# Hoff.net
KiCad netlist of a schematic drawn in EAGLE
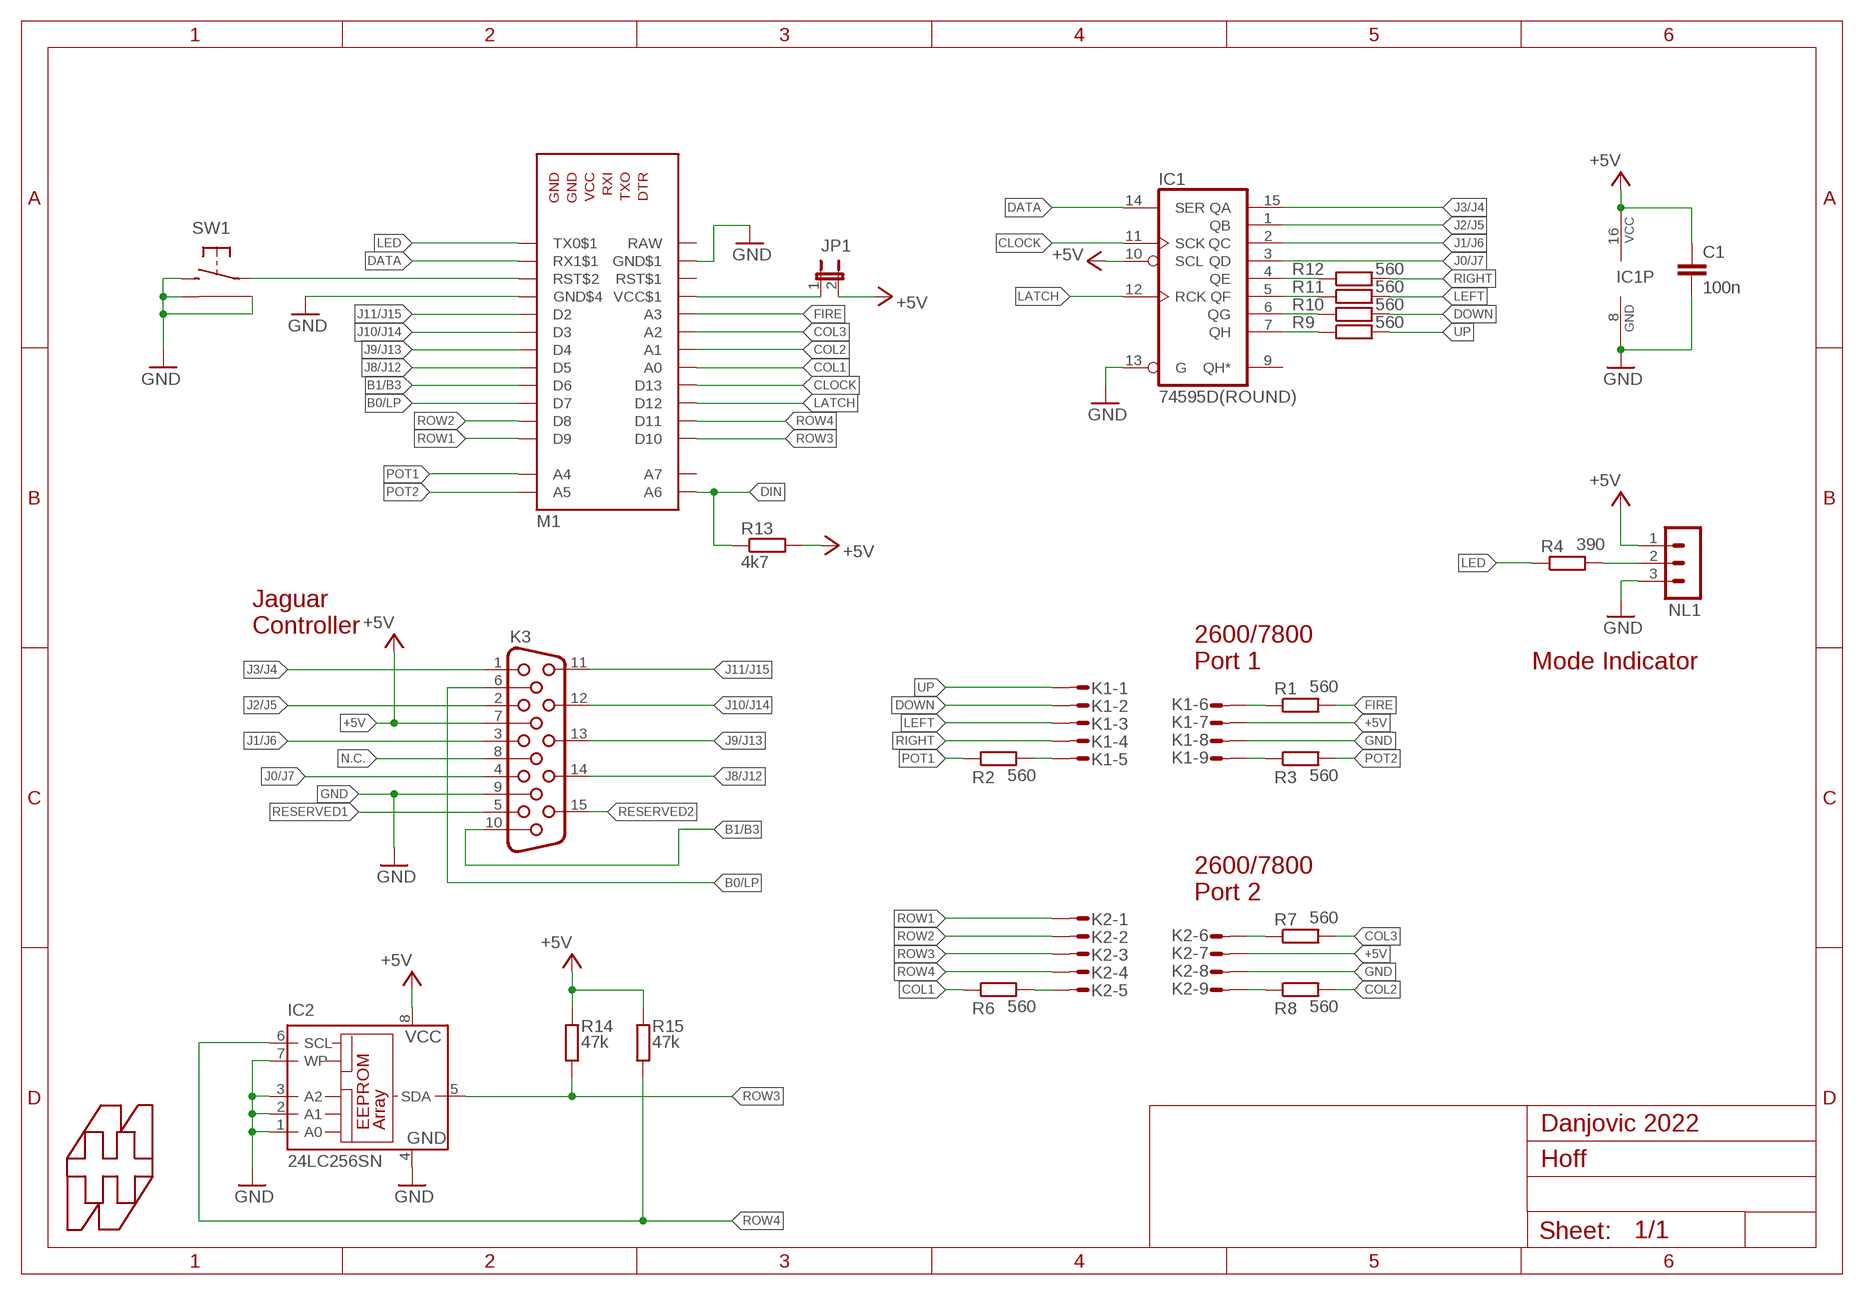
[diagram p0: schematic, sheet 1]

(export (version "E")
  (design (tool "Eeschema 10.0.6"))
  (components
    (comp (ref "C1")
      (value "100n")
      (footprint "eagle-import:C050-024X044")
      (libsource (lib "eagle-import") (part "C-EU050-024X044"))
    )
    (comp (ref "IC1")
      (value "74595D(ROUND)")
      (footprint "eagle-import:DIL16-ROUND")
      (libsource (lib "eagle-import") (part "74595D(ROUND)"))
    )
    (comp (ref "IC2")
      (value "24LC256SN")
      (footprint "eagle-import:SO-08")
      (fields (field (name "MF") "MICROCHIP") (field (name "MPN") "24LC256-I/SN"))
      (libsource (lib "eagle-import") (part "24SNLC256"))
    )
    (comp (ref "JP1")
      (value "JP1E")
      (footprint "eagle-import:JP1")
      (libsource (lib "eagle-import") (part "JP1E"))
    )
    (comp (ref "K1")
      (value "S09P")
      (footprint "eagle-import:S09P")
      (libsource (lib "eagle-import") (part "S09P"))
    )
    (comp (ref "K2")
      (value "S09P")
      (footprint "eagle-import:S09P")
      (libsource (lib "eagle-import") (part "S09P"))
    )
    (comp (ref "K3")
      (value "HF15H")
      (footprint "eagle-import:HDF15H")
      (libsource (lib "eagle-import") (part "HF15H"))
    )
    (comp (ref "M1")
      (value "ARDUINO_PRO_MINI_SIDE_ONLY")
      (footprint "eagle-import:ARDUNIO_PRO_MINI_SIDE_ONLY")
      (libsource (lib "eagle-import") (part "ARDUINO_PRO_MINI_SIDE_ONLY"))
    )
    (comp (ref "NL1")
      (value "MA03-1")
      (footprint "eagle-import:MA03-1")
      (libsource (lib "eagle-import") (part "MA03-1"))
    )
    (comp (ref "R1")
      (value "560")
      (footprint "eagle-import:0204_7")
      (libsource (lib "eagle-import") (part "R-EU_0204/7"))
    )
    (comp (ref "R2")
      (value "560")
      (footprint "eagle-import:0204_7")
      (libsource (lib "eagle-import") (part "R-EU_0204/7"))
    )
    (comp (ref "R3")
      (value "560")
      (footprint "eagle-import:0204_7")
      (libsource (lib "eagle-import") (part "R-EU_0204/7"))
    )
    (comp (ref "R4")
      (value "390")
      (footprint "eagle-import:0204_7")
      (libsource (lib "eagle-import") (part "R-EU_0204/7"))
    )
    (comp (ref "R6")
      (value "560")
      (footprint "eagle-import:0204_7")
      (libsource (lib "eagle-import") (part "R-EU_0204/7"))
    )
    (comp (ref "R7")
      (value "560")
      (footprint "eagle-import:0204_7")
      (libsource (lib "eagle-import") (part "R-EU_0204/7"))
    )
    (comp (ref "R8")
      (value "560")
      (footprint "eagle-import:0204_7")
      (libsource (lib "eagle-import") (part "R-EU_0204/7"))
    )
    (comp (ref "R9")
      (value "560")
      (footprint "eagle-import:0204_7")
      (libsource (lib "eagle-import") (part "R-EU_0204/7"))
    )
    (comp (ref "R10")
      (value "560")
      (footprint "eagle-import:0204_7")
      (libsource (lib "eagle-import") (part "R-EU_0204/7"))
    )
    (comp (ref "R11")
      (value "560")
      (footprint "eagle-import:0204_7")
      (libsource (lib "eagle-import") (part "R-EU_0204/7"))
    )
    (comp (ref "R12")
      (value "560")
      (footprint "eagle-import:0204_7")
      (libsource (lib "eagle-import") (part "R-EU_0204/7"))
    )
    (comp (ref "R13")
      (value "4k7")
      (footprint "eagle-import:0204_7")
      (libsource (lib "eagle-import") (part "R-EU_0204/7"))
    )
    (comp (ref "R14")
      (value "47k")
      (footprint "eagle-import:0204_7")
      (libsource (lib "eagle-import") (part "R-EU_0204/7"))
    )
    (comp (ref "R15")
      (value "47k")
      (footprint "eagle-import:0204_7")
      (libsource (lib "eagle-import") (part "R-EU_0204/7"))
    )
    (comp (ref "SW")
      (value "31-XX-GG")
      (footprint "eagle-import:B3F-31XX")
      (libsource (lib "eagle-import") (part "31-XX-GG"))
    )
    (comp (ref "U$1")
      (value "HAMMOND-1593J")
      (footprint "eagle-import:1593J")
      (libsource (lib "eagle-import") (part "HAMMOND-1593J"))
    )
  )
  (nets
    (net (code "1") (name "+5V") (class "Default")
      (node (ref "C1") (pin "1") (pinfunction "1_1") (pintype "passive"))
      (node (ref "IC1") (pin "10") (pinfunction "SCL_10") (pintype "input"))
      (node (ref "IC1") (pin "16") (pinfunction "VCC_16") (pintype "power_in"))
      (node (ref "IC2") (pin "8") (pinfunction "VCC_8") (pintype "power_in"))
      (node (ref "JP1") (pin "2") (pinfunction "2_2") (pintype "passive"))
      (node (ref "K1") (pin "7") (pinfunction "S_7") (pintype "passive"))
      (node (ref "K2") (pin "7") (pinfunction "S_7") (pintype "passive"))
      (node (ref "K3") (pin "7") (pinfunction "7_7") (pintype "passive"))
      (node (ref "NL1") (pin "1") (pinfunction "1_1") (pintype "passive"))
      (node (ref "R13") (pin "2") (pinfunction "2_2") (pintype "passive"))
      (node (ref "R14") (pin "2") (pinfunction "2_2") (pintype "passive"))
      (node (ref "R15") (pin "2") (pinfunction "2_2") (pintype "passive"))
    )
    (net (code "2") (name "/RAW") (class "Default")
      (node (ref "M1") (pin "RAW") (pinfunction "RAW_RAW") (pintype "power_in"))
    )
    (net (code "3") (name "B0{slash}LP") (class "Default")
      (node (ref "K3") (pin "6") (pinfunction "6_6") (pintype "passive"))
      (node (ref "M1") (pin "D7") (pinfunction "D7_D7") (pintype "bidirectional"))
    )
    (net (code "4") (name "B1{slash}B3") (class "Default")
      (node (ref "K3") (pin "10") (pinfunction "10_10") (pintype "passive"))
      (node (ref "M1") (pin "D6") (pinfunction "D6_D6") (pintype "bidirectional"))
    )
    (net (code "5") (name "CLOCK") (class "Default")
      (node (ref "IC1") (pin "11") (pinfunction "SCK_11") (pintype "input"))
      (node (ref "M1") (pin "D13") (pinfunction "D13_D13") (pintype "bidirectional"))
    )
    (net (code "6") (name "COL1") (class "Default")
      (node (ref "M1") (pin "A0") (pinfunction "A0_A0") (pintype "bidirectional"))
      (node (ref "R6") (pin "1") (pinfunction "1_1") (pintype "passive"))
    )
    (net (code "7") (name "COL2") (class "Default")
      (node (ref "M1") (pin "A1") (pinfunction "A1_A1") (pintype "bidirectional"))
      (node (ref "R8") (pin "2") (pinfunction "2_2") (pintype "passive"))
    )
    (net (code "8") (name "COL3") (class "Default")
      (node (ref "M1") (pin "A2") (pinfunction "A2_A2") (pintype "bidirectional"))
      (node (ref "R7") (pin "2") (pinfunction "2_2") (pintype "passive"))
    )
    (net (code "9") (name "DATA") (class "Default")
      (node (ref "IC1") (pin "14") (pinfunction "SER_14") (pintype "input"))
      (node (ref "M1") (pin "RX1$1") (pinfunction "RX1$1_RX1$1") (pintype "bidirectional"))
    )
    (net (code "10") (name "DIN") (class "Default")
      (node (ref "M1") (pin "A6") (pinfunction "A6_A6") (pintype "input"))
      (node (ref "R13") (pin "1") (pinfunction "1_1") (pintype "passive"))
    )
    (net (code "11") (name "DOWN") (class "Default")
      (node (ref "K1") (pin "2") (pinfunction "S_2") (pintype "passive"))
      (node (ref "R10") (pin "2") (pinfunction "2_2") (pintype "passive"))
    )
    (net (code "12") (name "FIRE") (class "Default")
      (node (ref "M1") (pin "A3") (pinfunction "A3_A3") (pintype "bidirectional"))
      (node (ref "R1") (pin "2") (pinfunction "2_2") (pintype "passive"))
    )
    (net (code "13") (name "GND") (class "Default")
      (node (ref "C1") (pin "2") (pinfunction "2_2") (pintype "passive"))
      (node (ref "IC1") (pin "13") (pinfunction "G_13") (pintype "input"))
      (node (ref "IC1") (pin "8") (pinfunction "GND_8") (pintype "power_in"))
      (node (ref "IC2") (pin "1") (pinfunction "A0_1") (pintype "input"))
      (node (ref "IC2") (pin "2") (pinfunction "A1_2") (pintype "input"))
      (node (ref "IC2") (pin "3") (pinfunction "A2_3") (pintype "input"))
      (node (ref "IC2") (pin "4") (pinfunction "GND_4") (pintype "power_in"))
      (node (ref "IC2") (pin "7") (pinfunction "WP_7") (pintype "input"))
      (node (ref "K1") (pin "8") (pinfunction "S_8") (pintype "passive"))
      (node (ref "K2") (pin "8") (pinfunction "S_8") (pintype "passive"))
      (node (ref "K3") (pin "9") (pinfunction "9_9") (pintype "passive"))
      (node (ref "M1") (pin "GDN$1") (pinfunction "GND$1_GDN$1") (pintype "power_in"))
      (node (ref "M1") (pin "GND$4") (pinfunction "GND$4_GND$4") (pintype "power_in"))
      (node (ref "NL1") (pin "3") (pinfunction "3_3") (pintype "passive"))
      (node (ref "SW") (pin "2") (pinfunction "S_2") (pintype "passive"))
      (node (ref "SW") (pin "3") (pinfunction "G$1_3") (pintype "passive"))
      (node (ref "SW") (pin "4") (pinfunction "G$2_4") (pintype "passive"))
    )
    (net (code "14") (name "J0{slash}J7") (class "Default")
      (node (ref "IC1") (pin "3") (pinfunction "QD_3") (pintype "tri_state"))
      (node (ref "K3") (pin "4") (pinfunction "4_4") (pintype "passive"))
    )
    (net (code "15") (name "J1{slash}J6") (class "Default")
      (node (ref "IC1") (pin "2") (pinfunction "QC_2") (pintype "tri_state"))
      (node (ref "K3") (pin "3") (pinfunction "3_3") (pintype "passive"))
    )
    (net (code "16") (name "J2{slash}J5") (class "Default")
      (node (ref "IC1") (pin "1") (pinfunction "QB_1") (pintype "tri_state"))
      (node (ref "K3") (pin "2") (pinfunction "2_2") (pintype "passive"))
    )
    (net (code "17") (name "J3{slash}J4") (class "Default")
      (node (ref "IC1") (pin "15") (pinfunction "QA_15") (pintype "tri_state"))
      (node (ref "K3") (pin "1") (pinfunction "1_1") (pintype "passive"))
    )
    (net (code "18") (name "J8{slash}J12") (class "Default")
      (node (ref "K3") (pin "14") (pinfunction "14_14") (pintype "passive"))
      (node (ref "M1") (pin "D5") (pinfunction "D5_D5") (pintype "bidirectional"))
    )
    (net (code "19") (name "J9{slash}J13") (class "Default")
      (node (ref "K3") (pin "13") (pinfunction "13_13") (pintype "passive"))
      (node (ref "M1") (pin "D4") (pinfunction "D4_D4") (pintype "bidirectional"))
    )
    (net (code "20") (name "J10{slash}J14") (class "Default")
      (node (ref "K3") (pin "12") (pinfunction "12_12") (pintype "passive"))
      (node (ref "M1") (pin "D3") (pinfunction "D3_D3") (pintype "bidirectional"))
    )
    (net (code "21") (name "J11{slash}J15") (class "Default")
      (node (ref "K3") (pin "11") (pinfunction "11_11") (pintype "passive"))
      (node (ref "M1") (pin "D2") (pinfunction "D2_D2") (pintype "bidirectional"))
    )
    (net (code "22") (name "LATCH") (class "Default")
      (node (ref "IC1") (pin "12") (pinfunction "RCK_12") (pintype "input"))
      (node (ref "M1") (pin "D12") (pinfunction "D12_D12") (pintype "bidirectional"))
    )
    (net (code "23") (name "LED") (class "Default")
      (node (ref "M1") (pin "TX0$1") (pinfunction "TX0$1_TX0$1") (pintype "bidirectional"))
      (node (ref "R4") (pin "1") (pinfunction "1_1") (pintype "passive"))
    )
    (net (code "24") (name "LEFT") (class "Default")
      (node (ref "K1") (pin "3") (pinfunction "S_3") (pintype "passive"))
      (node (ref "R11") (pin "2") (pinfunction "2_2") (pintype "passive"))
    )
    (net (code "25") (name "N.C.") (class "Default")
      (node (ref "K3") (pin "8") (pinfunction "8_8") (pintype "passive"))
    )
    (net (code "26") (name "Net-(IC1A-QE)") (class "Default")
      (node (ref "IC1") (pin "4") (pinfunction "QE_4") (pintype "tri_state"))
      (node (ref "R12") (pin "1") (pinfunction "1_1") (pintype "passive"))
    )
    (net (code "27") (name "Net-(IC1A-QF)") (class "Default")
      (node (ref "IC1") (pin "5") (pinfunction "QF_5") (pintype "tri_state"))
      (node (ref "R11") (pin "1") (pinfunction "1_1") (pintype "passive"))
    )
    (net (code "28") (name "Net-(IC1A-QG)") (class "Default")
      (node (ref "IC1") (pin "6") (pinfunction "QG_6") (pintype "tri_state"))
      (node (ref "R10") (pin "1") (pinfunction "1_1") (pintype "passive"))
    )
    (net (code "29") (name "Net-(IC1A-QH)") (class "Default")
      (node (ref "IC1") (pin "7") (pinfunction "QH_7") (pintype "tri_state"))
      (node (ref "R9") (pin "1") (pinfunction "1_1") (pintype "passive"))
    )
    (net (code "30") (name "Net-(JP1-Pad1)") (class "Default")
      (node (ref "JP1") (pin "1") (pinfunction "1_1") (pintype "passive"))
      (node (ref "M1") (pin "VCC$1") (pinfunction "VCC$1_VCC$1") (pintype "power_in"))
    )
    (net (code "31") (name "Net-(K1E-S)") (class "Default")
      (node (ref "K1") (pin "5") (pinfunction "S_5") (pintype "passive"))
      (node (ref "R2") (pin "2") (pinfunction "2_2") (pintype "passive"))
    )
    (net (code "32") (name "Net-(K1F-S)") (class "Default")
      (node (ref "K1") (pin "6") (pinfunction "S_6") (pintype "passive"))
      (node (ref "R1") (pin "1") (pinfunction "1_1") (pintype "passive"))
    )
    (net (code "33") (name "Net-(K1I-S)") (class "Default")
      (node (ref "K1") (pin "9") (pinfunction "S_9") (pintype "passive"))
      (node (ref "R3") (pin "1") (pinfunction "1_1") (pintype "passive"))
    )
    (net (code "34") (name "Net-(K2E-S)") (class "Default")
      (node (ref "K2") (pin "5") (pinfunction "S_5") (pintype "passive"))
      (node (ref "R6") (pin "2") (pinfunction "2_2") (pintype "passive"))
    )
    (net (code "35") (name "Net-(K2F-S)") (class "Default")
      (node (ref "K2") (pin "6") (pinfunction "S_6") (pintype "passive"))
      (node (ref "R7") (pin "1") (pinfunction "1_1") (pintype "passive"))
    )
    (net (code "36") (name "Net-(K2I-S)") (class "Default")
      (node (ref "K2") (pin "9") (pinfunction "S_9") (pintype "passive"))
      (node (ref "R8") (pin "1") (pinfunction "1_1") (pintype "passive"))
    )
    (net (code "37") (name "Net-(NL1-Pad2)") (class "Default")
      (node (ref "NL1") (pin "2") (pinfunction "2_2") (pintype "passive"))
      (node (ref "R4") (pin "2") (pinfunction "2_2") (pintype "passive"))
    )
    (net (code "38") (name "Net-(SWA-P)") (class "Default")
      (node (ref "M1") (pin "RST$2") (pinfunction "RST$2_RST$2") (pintype "input"))
      (node (ref "SW") (pin "1") (pinfunction "P_1") (pintype "passive"))
    )
    (net (code "39") (name "POT1") (class "Default")
      (node (ref "M1") (pin "A4") (pinfunction "A4_A4") (pintype "bidirectional"))
      (node (ref "R2") (pin "1") (pinfunction "1_1") (pintype "passive"))
    )
    (net (code "40") (name "POT2") (class "Default")
      (node (ref "M1") (pin "A5") (pinfunction "A5_A5") (pintype "bidirectional"))
      (node (ref "R3") (pin "2") (pinfunction "2_2") (pintype "passive"))
    )
    (net (code "41") (name "RESERVED1") (class "Default")
      (node (ref "K3") (pin "5") (pinfunction "5_5") (pintype "passive"))
    )
    (net (code "42") (name "RESERVED2") (class "Default")
      (node (ref "K3") (pin "15") (pinfunction "15_15") (pintype "passive"))
    )
    (net (code "43") (name "RIGHT") (class "Default")
      (node (ref "K1") (pin "4") (pinfunction "S_4") (pintype "passive"))
      (node (ref "R12") (pin "2") (pinfunction "2_2") (pintype "passive"))
    )
    (net (code "44") (name "ROW1") (class "Default")
      (node (ref "K2") (pin "1") (pinfunction "S_1") (pintype "passive"))
      (node (ref "M1") (pin "D9") (pinfunction "D9_D9") (pintype "bidirectional"))
    )
    (net (code "45") (name "ROW2") (class "Default")
      (node (ref "K2") (pin "2") (pinfunction "S_2") (pintype "passive"))
      (node (ref "M1") (pin "D8") (pinfunction "D8_D8") (pintype "bidirectional"))
    )
    (net (code "46") (name "ROW3") (class "Default")
      (node (ref "IC2") (pin "5") (pinfunction "SDA_5") (pintype "bidirectional"))
      (node (ref "K2") (pin "3") (pinfunction "S_3") (pintype "passive"))
      (node (ref "M1") (pin "D10") (pinfunction "D10_D10") (pintype "bidirectional"))
      (node (ref "R14") (pin "1") (pinfunction "1_1") (pintype "passive"))
    )
    (net (code "47") (name "ROW4") (class "Default")
      (node (ref "IC2") (pin "6") (pinfunction "SCL_6") (pintype "input"))
      (node (ref "K2") (pin "4") (pinfunction "S_4") (pintype "passive"))
      (node (ref "M1") (pin "D11") (pinfunction "D11_D11") (pintype "bidirectional"))
      (node (ref "R15") (pin "1") (pinfunction "1_1") (pintype "passive"))
    )
    (net (code "48") (name "UP") (class "Default")
      (node (ref "K1") (pin "1") (pinfunction "S_1") (pintype "passive"))
      (node (ref "R9") (pin "2") (pinfunction "2_2") (pintype "passive"))
    )
    (net (code "49") (name "unconnected-(IC1A-QH*-Pad9)") (class "Default")
      (node (ref "IC1") (pin "9") (pinfunction "QH*_9") (pintype "tri_state"))
    )
    (net (code "50") (name "unconnected-(M1-PadA7)") (class "Default")
      (node (ref "M1") (pin "A7") (pinfunction "A7_A7") (pintype "input"))
    )
    (net (code "51") (name "unconnected-(M1-PadRST$1)") (class "Default")
      (node (ref "M1") (pin "RST$1") (pinfunction "RST$1_RST$1") (pintype "input"))
    )
  )
)
